# BTsoundCard_Proto_R1.net
KiCad netlist of a schematic drawn in EAGLE
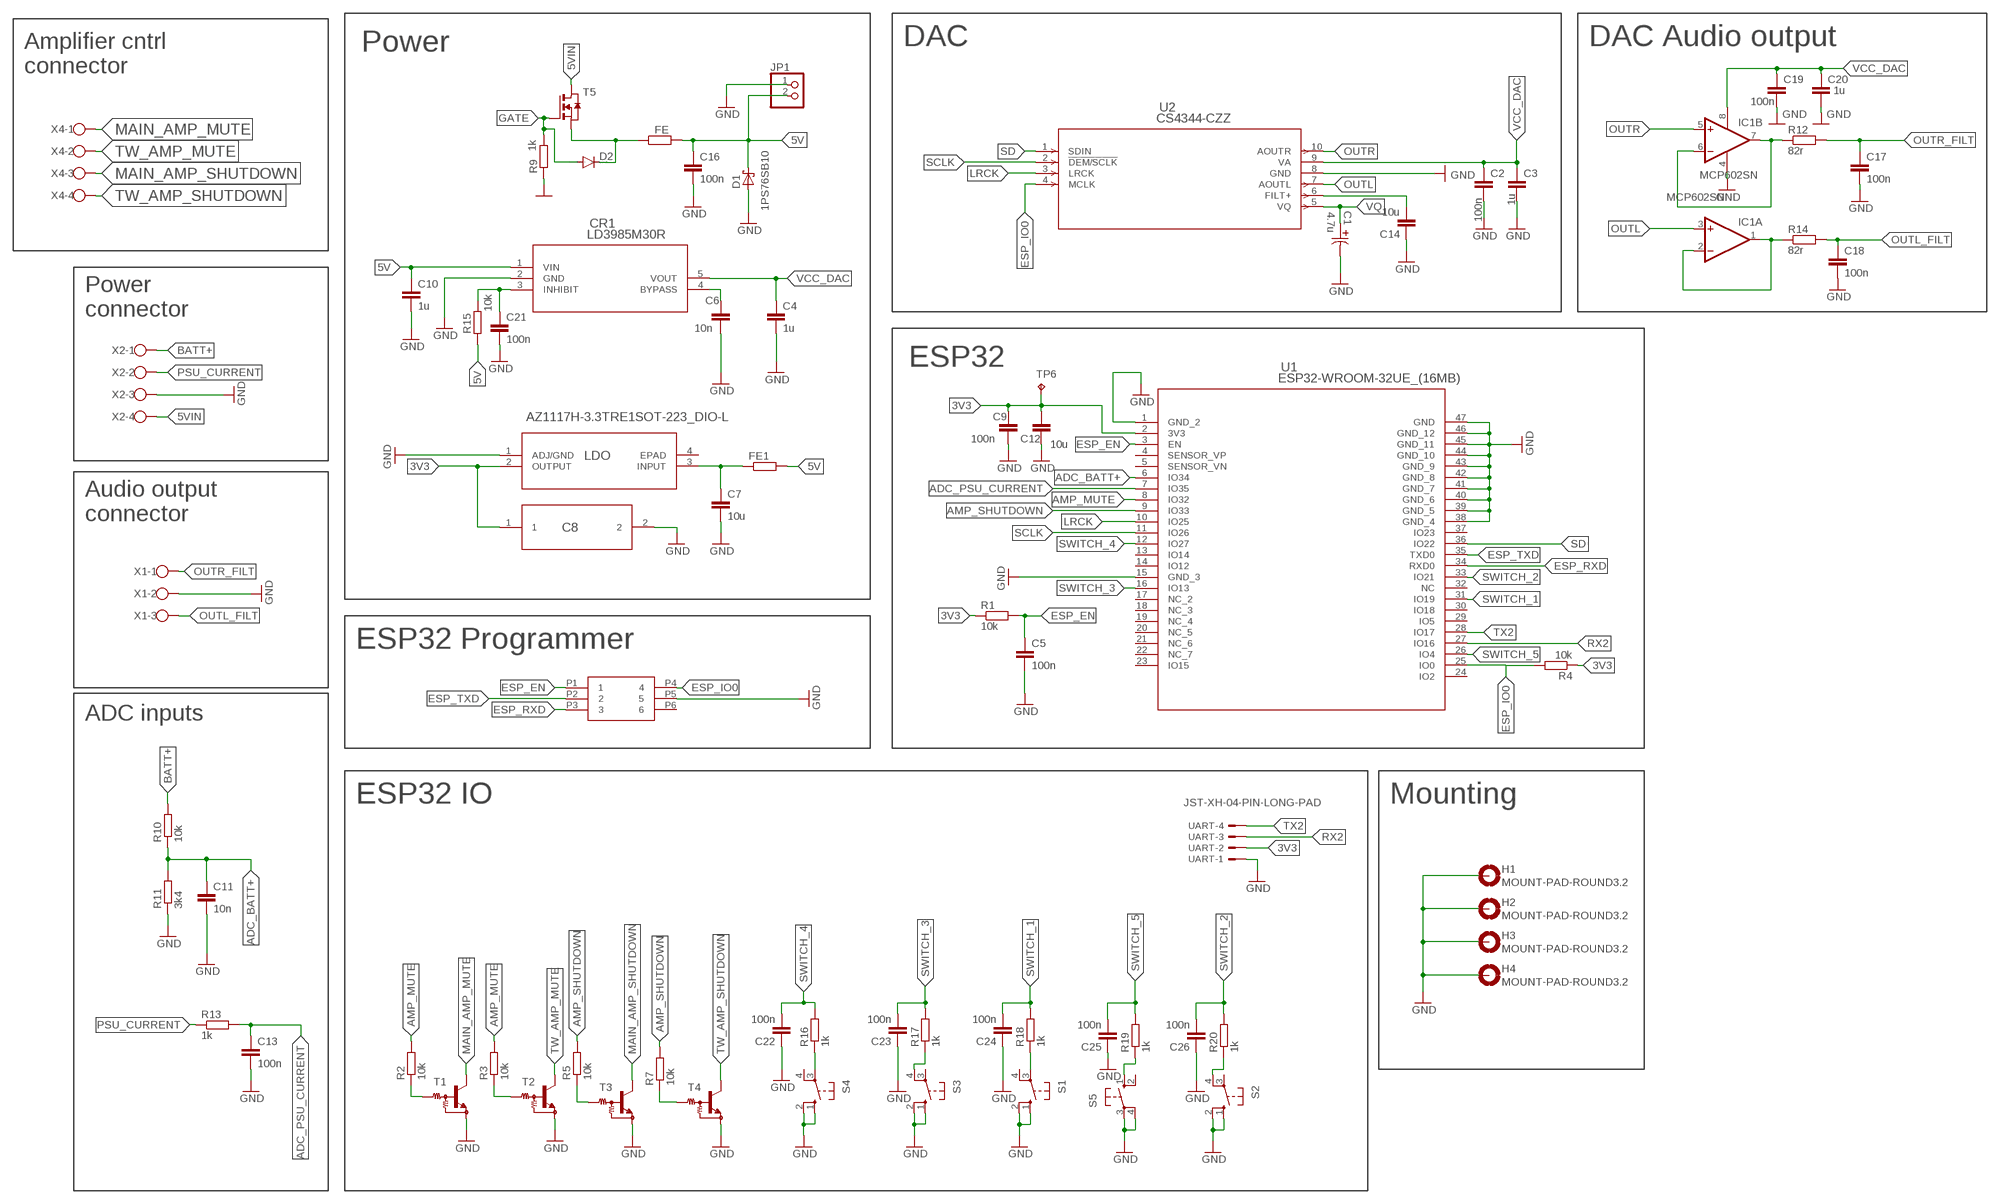
[diagram p0: schematic, sheet 1]

(export (version "E")
  (design (tool "Eeschema 10.0.6"))
  (components
    (comp (ref "C1")
      (value "4.7u")
      (footprint "eagle-import:CAP_EEFK_B_PAN-M")
      (fields (field (name "MANUFACTURER_PART_NUMBER") "EEEFK1H4R7R"))
      (libsource (lib "eagle-import") (part "EEEFK1H4R7RCAP_EEFK_B_PAN-M"))
    )
    (comp (ref "C2")
      (value "100n")
      (footprint "eagle-import:C0603")
      (libsource (lib "eagle-import") (part "C-EUC0603"))
    )
    (comp (ref "C3")
      (value "1u")
      (footprint "eagle-import:C0603")
      (libsource (lib "eagle-import") (part "C-EUC0603"))
    )
    (comp (ref "C4")
      (value "1u")
      (footprint "eagle-import:C0603")
      (libsource (lib "eagle-import") (part "C-EUC0603"))
    )
    (comp (ref "C5")
      (value "100n")
      (footprint "eagle-import:C0603")
      (libsource (lib "eagle-import") (part "C-EUC0603"))
    )
    (comp (ref "C6")
      (value "10n")
      (footprint "eagle-import:C0603")
      (libsource (lib "eagle-import") (part "C-EUC0603"))
    )
    (comp (ref "C7")
      (value "10u")
      (footprint "eagle-import:C0805")
      (libsource (lib "eagle-import") (part "C-EUC0805"))
    )
    (comp (ref "C8")
      (value "TPSC336K010R0375")
      (footprint "eagle-import:TPSC336K010R0375_AVX")
      (fields (field (name "COPYRIGHT") "Copyright (C) 2018 Accelerated Designs. All rights reserved"))
      (libsource (lib "eagle-import") (part "TPSC336K010R0375"))
    )
    (comp (ref "C9")
      (value "100n")
      (footprint "eagle-import:C0603")
      (libsource (lib "eagle-import") (part "C-EUC0603"))
    )
    (comp (ref "C10")
      (value "1u")
      (footprint "eagle-import:C0603")
      (libsource (lib "eagle-import") (part "C-EUC0603"))
    )
    (comp (ref "C11")
      (value "10n")
      (footprint "eagle-import:C0603")
      (libsource (lib "eagle-import") (part "C-EUC0603"))
    )
    (comp (ref "C12")
      (value "10u")
      (footprint "eagle-import:C0805")
      (libsource (lib "eagle-import") (part "C-EUC0805"))
    )
    (comp (ref "C13")
      (value "100n")
      (footprint "eagle-import:C0603")
      (libsource (lib "eagle-import") (part "C-EUC0603"))
    )
    (comp (ref "C14")
      (value "10u")
      (footprint "eagle-import:C0805")
      (libsource (lib "eagle-import") (part "C-EUC0805"))
    )
    (comp (ref "C16")
      (value "100n")
      (footprint "eagle-import:C0603")
      (libsource (lib "eagle-import") (part "C-EUC0603"))
    )
    (comp (ref "C17")
      (value "100n")
      (footprint "eagle-import:C0603")
      (libsource (lib "eagle-import") (part "C-EUC0603"))
    )
    (comp (ref "C18")
      (value "100n")
      (footprint "eagle-import:C0603")
      (libsource (lib "eagle-import") (part "C-EUC0603"))
    )
    (comp (ref "C19")
      (value "100n")
      (footprint "eagle-import:C0603")
      (libsource (lib "eagle-import") (part "C-EUC0603"))
    )
    (comp (ref "C20")
      (value "1u")
      (footprint "eagle-import:C0603")
      (libsource (lib "eagle-import") (part "C-EUC0603"))
    )
    (comp (ref "C21")
      (value "100n")
      (footprint "eagle-import:C0603")
      (libsource (lib "eagle-import") (part "C-EUC0603"))
    )
    (comp (ref "C22")
      (value "100n")
      (footprint "eagle-import:C0603")
      (libsource (lib "eagle-import") (part "C-EUC0603"))
    )
    (comp (ref "C23")
      (value "100n")
      (footprint "eagle-import:C0603")
      (libsource (lib "eagle-import") (part "C-EUC0603"))
    )
    (comp (ref "C24")
      (value "100n")
      (footprint "eagle-import:C0603")
      (libsource (lib "eagle-import") (part "C-EUC0603"))
    )
    (comp (ref "C25")
      (value "100n")
      (footprint "eagle-import:C0603")
      (libsource (lib "eagle-import") (part "C-EUC0603"))
    )
    (comp (ref "C26")
      (value "100n")
      (footprint "eagle-import:C0603")
      (libsource (lib "eagle-import") (part "C-EUC0603"))
    )
    (comp (ref "CR1")
      (value "LD3985M30R")
      (footprint "eagle-import:SOT23-5L_STM")
      (fields (field (name "COPYRIGHT") "Copyright (C) 2023 Ultra Librarian. All rights reserved."))
      (libsource (lib "eagle-import") (part "LD3985M30R"))
    )
    (comp (ref "D1")
      (value "1PS76SB10")
      (footprint "eagle-import:SOD323(F)")
      (libsource (lib "eagle-import") (part "1PS76SB10"))
    )
    (comp (ref "D2")
      (value "5.1V")
      (footprint "eagle-import:MINIMELF")
      (libsource (lib "eagle-import") (part "DIODE-MINIMELF"))
    )
    (comp (ref "FE")
      (value "R-EU_R0805")
      (footprint "eagle-import:R0805")
      (libsource (lib "eagle-import") (part "R-EU_R0805"))
    )
    (comp (ref "FE1")
      (value "R-EU_R0805")
      (footprint "eagle-import:R0805")
      (libsource (lib "eagle-import") (part "R-EU_R0805"))
    )
    (comp (ref "H1")
      (value "MOUNT-PAD-ROUND3.2")
      (footprint "eagle-import:3,2-PAD")
      (libsource (lib "eagle-import") (part "MOUNT-PAD-ROUND3.2"))
    )
    (comp (ref "H2")
      (value "MOUNT-PAD-ROUND3.2")
      (footprint "eagle-import:3,2-PAD")
      (libsource (lib "eagle-import") (part "MOUNT-PAD-ROUND3.2"))
    )
    (comp (ref "H3")
      (value "MOUNT-PAD-ROUND3.2")
      (footprint "eagle-import:3,2-PAD")
      (libsource (lib "eagle-import") (part "MOUNT-PAD-ROUND3.2"))
    )
    (comp (ref "H4")
      (value "MOUNT-PAD-ROUND3.2")
      (footprint "eagle-import:3,2-PAD")
      (libsource (lib "eagle-import") (part "MOUNT-PAD-ROUND3.2"))
    )
    (comp (ref "IC1")
      (value "MCP602SN")
      (footprint "eagle-import:SO08")
      (libsource (lib "eagle-import") (part "MCP602SN"))
    )
    (comp (ref "JP1")
      (value "PINHD-1X2")
      (footprint "eagle-import:1X02")
      (libsource (lib "eagle-import") (part "PINHD-1X2"))
    )
    (comp (ref "LDO")
      (value "AZ1117H-3.3TRE1SOT-223_DIO-L")
      (footprint "eagle-import:SOT-223_DIO-L")
      (fields (field (name "MANUFACTURER_PART_NUMBER") "AZ1117H-3.3TRE1"))
      (libsource (lib "eagle-import") (part "AZ1117H-3.3TRE1SOT-223_DIO-L"))
    )
    (comp (ref "R1")
      (value "10k")
      (footprint "eagle-import:R0603")
      (libsource (lib "eagle-import") (part "R-EU_R0603"))
    )
    (comp (ref "R2")
      (value "10k")
      (footprint "eagle-import:R0603")
      (libsource (lib "eagle-import") (part "R-EU_R0603"))
    )
    (comp (ref "R3")
      (value "10k")
      (footprint "eagle-import:R0603")
      (libsource (lib "eagle-import") (part "R-EU_R0603"))
    )
    (comp (ref "R4")
      (value "10k")
      (footprint "eagle-import:R0603")
      (libsource (lib "eagle-import") (part "R-EU_R0603"))
    )
    (comp (ref "R5")
      (value "10k")
      (footprint "eagle-import:R0603")
      (libsource (lib "eagle-import") (part "R-EU_R0603"))
    )
    (comp (ref "R7")
      (value "10k")
      (footprint "eagle-import:R0603")
      (libsource (lib "eagle-import") (part "R-EU_R0603"))
    )
    (comp (ref "R9")
      (value "1k")
      (footprint "eagle-import:R1206")
      (libsource (lib "eagle-import") (part "R-EU_R1206"))
    )
    (comp (ref "R10")
      (value "10k")
      (footprint "eagle-import:R0805")
      (libsource (lib "eagle-import") (part "R-EU_R0805"))
    )
    (comp (ref "R11")
      (value "3k4")
      (footprint "eagle-import:R0603")
      (libsource (lib "eagle-import") (part "R-EU_R0603"))
    )
    (comp (ref "R12")
      (value "82r")
      (footprint "eagle-import:R1206")
      (libsource (lib "eagle-import") (part "R-EU_R1206"))
    )
    (comp (ref "R13")
      (value "1k")
      (footprint "eagle-import:R0603")
      (libsource (lib "eagle-import") (part "R-EU_R0603"))
    )
    (comp (ref "R14")
      (value "82r")
      (footprint "eagle-import:R1206")
      (libsource (lib "eagle-import") (part "R-EU_R1206"))
    )
    (comp (ref "R15")
      (value "10k")
      (footprint "eagle-import:R0603")
      (libsource (lib "eagle-import") (part "R-EU_R0603"))
    )
    (comp (ref "R16")
      (value "1k")
      (footprint "eagle-import:R0603")
      (libsource (lib "eagle-import") (part "R-EU_R0603"))
    )
    (comp (ref "R17")
      (value "1k")
      (footprint "eagle-import:R0603")
      (libsource (lib "eagle-import") (part "R-EU_R0603"))
    )
    (comp (ref "R18")
      (value "1k")
      (footprint "eagle-import:R0603")
      (libsource (lib "eagle-import") (part "R-EU_R0603"))
    )
    (comp (ref "R19")
      (value "1k")
      (footprint "eagle-import:R0603")
      (libsource (lib "eagle-import") (part "R-EU_R0603"))
    )
    (comp (ref "R20")
      (value "1k")
      (footprint "eagle-import:R0603")
      (libsource (lib "eagle-import") (part "R-EU_R0603"))
    )
    (comp (ref "S1")
      (value "10-XX")
      (footprint "eagle-import:B3F-10XX")
      (fields (field (name "MPN") "B3F-1000"))
      (libsource (lib "eagle-import") (part "10-XX"))
    )
    (comp (ref "S2")
      (value "10-XX")
      (footprint "eagle-import:B3F-10XX")
      (fields (field (name "MPN") "B3F-1000"))
      (libsource (lib "eagle-import") (part "10-XX"))
    )
    (comp (ref "S3")
      (value "10-XX")
      (footprint "eagle-import:B3F-10XX")
      (fields (field (name "MPN") "B3F-1000"))
      (libsource (lib "eagle-import") (part "10-XX"))
    )
    (comp (ref "S4")
      (value "10-XX")
      (footprint "eagle-import:B3F-10XX")
      (fields (field (name "MPN") "B3F-1000"))
      (libsource (lib "eagle-import") (part "10-XX"))
    )
    (comp (ref "S5")
      (value "10-XX")
      (footprint "eagle-import:B3F-10XX")
      (fields (field (name "MPN") "B3F-1000"))
      (libsource (lib "eagle-import") (part "10-XX"))
    )
    (comp (ref "T1")
      (value "MUN2212T1-NPN_DRIVER-SC59-BEC")
      (footprint "eagle-import:SC59-BEC")
      (libsource (lib "eagle-import") (part "-NPN_DRIVER-SC59-BECMUN2212T1"))
    )
    (comp (ref "T2")
      (value "MUN2212T1-NPN_DRIVER-SC59-BEC")
      (footprint "eagle-import:SC59-BEC")
      (libsource (lib "eagle-import") (part "-NPN_DRIVER-SC59-BECMUN2212T1"))
    )
    (comp (ref "T3")
      (value "MUN2212T1-NPN_DRIVER-SC59-BEC")
      (footprint "eagle-import:SC59-BEC")
      (libsource (lib "eagle-import") (part "-NPN_DRIVER-SC59-BECMUN2212T1"))
    )
    (comp (ref "T4")
      (value "MUN2212T1-NPN_DRIVER-SC59-BEC")
      (footprint "eagle-import:SC59-BEC")
      (libsource (lib "eagle-import") (part "-NPN_DRIVER-SC59-BECMUN2212T1"))
    )
    (comp (ref "T5")
      (value "NMOSSOT23")
      (footprint "eagle-import:SOT-23")
      (libsource (lib "eagle-import") (part "NMOSSOT23"))
    )
    (comp (ref "TP6")
      (value "TPPAD1-13")
      (footprint "eagle-import:P1-13")
      (libsource (lib "eagle-import") (part "TPPAD1-13"))
    )
    (comp (ref "U$3")
      (value "3X2")
      (footprint "eagle-import:2X3")
      (libsource (lib "eagle-import") (part "3X2"))
    )
    (comp (ref "U1")
      (value "ESP32-WROOM-32UE_(16MB)")
      (footprint "eagle-import:IC38_ESP32-WROOM-32UE_(16MB)_E")
      (fields
        (field (name "MANUFACTURER_PART_NUMBER") "ESP32-WROOM-32UE (16MB)")
        (field (name "COPYRIGHT") "Copyright (C) 2022 Ultra Librarian. All rights reserved.")
      )
      (libsource (lib "eagle-import") (part "ESP32-WROOM-32UE_(16MB)"))
    )
    (comp (ref "U2")
      (value "CS4344-CZZ")
      (footprint "eagle-import:CIR-TSSOP-10")
      (fields (field (name "COPYRIGHT") "Copyright (C) 2023 Ultra Librarian. All rights reserved."))
      (libsource (lib "eagle-import") (part "CS4344-CZZ"))
    )
    (comp (ref "UART")
      (value "JST-XH-04-PIN-LONG-PAD")
      (footprint "eagle-import:JST-XH-04-PACKAGE-LONG-PAD")
      (libsource (lib "eagle-import") (part "JST-XH-04-PIN-LONG-PAD"))
    )
    (comp (ref "X1")
      (value "W237-103")
      (footprint "eagle-import:W237-103")
      (fields (field (name "MPN") "237-103"))
      (libsource (lib "eagle-import") (part "W237-103"))
    )
    (comp (ref "X2")
      (value "W237-4")
      (footprint "eagle-import:W237-4")
      (libsource (lib "eagle-import") (part "W237-4"))
    )
    (comp (ref "X4")
      (value "W237-4")
      (footprint "eagle-import:W237-4")
      (libsource (lib "eagle-import") (part "W237-4"))
    )
  )
  (nets
    (net (code "1") (name "3V3") (class "Default")
      (node (ref "C12") (pin "2") (pinfunction "2_2") (pintype "passive"))
      (node (ref "C8") (pin "1") (pinfunction "1_1") (pintype "passive"))
      (node (ref "C9") (pin "1") (pinfunction "1_1") (pintype "passive"))
      (node (ref "LDO") (pin "2") (pinfunction "OUTPUT_2") (pintype "output"))
      (node (ref "R1") (pin "1") (pinfunction "1_1") (pintype "passive"))
      (node (ref "R4") (pin "1") (pinfunction "1_1") (pintype "passive"))
      (node (ref "TP6") (pin "TP") (pinfunction "TP_TP") (pintype "input"))
      (node (ref "U1") (pin "2") (pinfunction "3V3_2") (pintype "passive"))
      (node (ref "UART") (pin "2") (pinfunction "S_2") (pintype "passive"))
    )
    (net (code "2") (name "5V") (class "Default")
      (node (ref "C10") (pin "1") (pinfunction "1_1") (pintype "passive"))
      (node (ref "C16") (pin "1") (pinfunction "1_1") (pintype "passive"))
      (node (ref "CR1") (pin "1") (pinfunction "VIN_1") (pintype "power_in"))
      (node (ref "D1") (pin "1") (pinfunction "K_1") (pintype "passive"))
      (node (ref "FE") (pin "2") (pinfunction "2_2") (pintype "passive"))
      (node (ref "FE1") (pin "2") (pinfunction "2_2") (pintype "passive"))
      (node (ref "JP1") (pin "2") (pinfunction "2_2") (pintype "passive"))
      (node (ref "R15") (pin "1") (pinfunction "1_1") (pintype "passive"))
    )
    (net (code "3") (name "5VIN") (class "Default")
      (node (ref "T5") (pin "1") (pinfunction "D_1") (pintype "passive"))
      (node (ref "X2") (pin "4") (pinfunction "KL_4") (pintype "passive"))
    )
    (net (code "4") (name "ADC_BATT+") (class "Default")
      (node (ref "C11") (pin "1") (pinfunction "1_1") (pintype "passive"))
      (node (ref "R10") (pin "1") (pinfunction "1_1") (pintype "passive"))
      (node (ref "R11") (pin "2") (pinfunction "2_2") (pintype "passive"))
      (node (ref "U1") (pin "6") (pinfunction "IO34_6") (pintype "passive"))
    )
    (net (code "5") (name "ADC_PSU_CURRENT") (class "Default")
      (node (ref "C13") (pin "1") (pinfunction "1_1") (pintype "passive"))
      (node (ref "R13") (pin "2") (pinfunction "2_2") (pintype "passive"))
      (node (ref "U1") (pin "7") (pinfunction "IO35_7") (pintype "passive"))
    )
    (net (code "6") (name "AMP_MUTE") (class "Default")
      (node (ref "R2") (pin "2") (pinfunction "2_2") (pintype "passive"))
      (node (ref "R3") (pin "2") (pinfunction "2_2") (pintype "passive"))
      (node (ref "U1") (pin "8") (pinfunction "IO32_8") (pintype "passive"))
    )
    (net (code "7") (name "AMP_SHUTDOWN") (class "Default")
      (node (ref "R5") (pin "2") (pinfunction "2_2") (pintype "passive"))
      (node (ref "R7") (pin "2") (pinfunction "2_2") (pintype "passive"))
      (node (ref "U1") (pin "9") (pinfunction "IO33_9") (pintype "passive"))
    )
    (net (code "8") (name "BATT+") (class "Default")
      (node (ref "R10") (pin "2") (pinfunction "2_2") (pintype "passive"))
      (node (ref "X2") (pin "1") (pinfunction "KL_1") (pintype "passive"))
    )
    (net (code "9") (name "ESP_EN") (class "Default")
      (node (ref "C5") (pin "1") (pinfunction "1_1") (pintype "passive"))
      (node (ref "R1") (pin "2") (pinfunction "2_2") (pintype "passive"))
      (node (ref "U$3") (pin "P1") (pinfunction "1_P1") (pintype "bidirectional"))
      (node (ref "U1") (pin "3") (pinfunction "EN_3") (pintype "passive"))
    )
    (net (code "10") (name "ESP_IO0") (class "Default")
      (node (ref "R4") (pin "2") (pinfunction "2_2") (pintype "passive"))
      (node (ref "U$3") (pin "P4") (pinfunction "4_P4") (pintype "bidirectional"))
      (node (ref "U1") (pin "25") (pinfunction "IO0_25") (pintype "passive"))
      (node (ref "U2") (pin "4") (pinfunction "MCLK_4") (pintype "input"))
    )
    (net (code "11") (name "ESP_RXD") (class "Default")
      (node (ref "U$3") (pin "P3") (pinfunction "3_P3") (pintype "bidirectional"))
      (node (ref "U1") (pin "34") (pinfunction "RXD0_34") (pintype "passive"))
    )
    (net (code "12") (name "ESP_TXD") (class "Default")
      (node (ref "U$3") (pin "P2") (pinfunction "2_P2") (pintype "bidirectional"))
      (node (ref "U1") (pin "35") (pinfunction "TXD0_35") (pintype "passive"))
    )
    (net (code "13") (name "GATE") (class "Default")
      (node (ref "D2") (pin "A") (pinfunction "A_A") (pintype "passive"))
      (node (ref "R9") (pin "2") (pinfunction "2_2") (pintype "passive"))
      (node (ref "T5") (pin "3") (pinfunction "G_3") (pintype "passive"))
    )
    (net (code "14") (name "GND") (class "Default")
      (node (ref "C1") (pin "2") (pinfunction "2_2") (pintype "passive"))
      (node (ref "C10") (pin "2") (pinfunction "2_2") (pintype "passive"))
      (node (ref "C11") (pin "2") (pinfunction "2_2") (pintype "passive"))
      (node (ref "C12") (pin "1") (pinfunction "1_1") (pintype "passive"))
      (node (ref "C13") (pin "2") (pinfunction "2_2") (pintype "passive"))
      (node (ref "C14") (pin "1") (pinfunction "1_1") (pintype "passive"))
      (node (ref "C16") (pin "2") (pinfunction "2_2") (pintype "passive"))
      (node (ref "C17") (pin "2") (pinfunction "2_2") (pintype "passive"))
      (node (ref "C18") (pin "2") (pinfunction "2_2") (pintype "passive"))
      (node (ref "C19") (pin "2") (pinfunction "2_2") (pintype "passive"))
      (node (ref "C2") (pin "2") (pinfunction "2_2") (pintype "passive"))
      (node (ref "C20") (pin "2") (pinfunction "2_2") (pintype "passive"))
      (node (ref "C21") (pin "2") (pinfunction "2_2") (pintype "passive"))
      (node (ref "C22") (pin "1") (pinfunction "1_1") (pintype "passive"))
      (node (ref "C23") (pin "1") (pinfunction "1_1") (pintype "passive"))
      (node (ref "C24") (pin "1") (pinfunction "1_1") (pintype "passive"))
      (node (ref "C25") (pin "1") (pinfunction "1_1") (pintype "passive"))
      (node (ref "C26") (pin "1") (pinfunction "1_1") (pintype "passive"))
      (node (ref "C3") (pin "2") (pinfunction "2_2") (pintype "passive"))
      (node (ref "C4") (pin "2") (pinfunction "2_2") (pintype "passive"))
      (node (ref "C5") (pin "2") (pinfunction "2_2") (pintype "passive"))
      (node (ref "C6") (pin "2") (pinfunction "2_2") (pintype "passive"))
      (node (ref "C7") (pin "2") (pinfunction "2_2") (pintype "passive"))
      (node (ref "C8") (pin "2") (pinfunction "2_2") (pintype "passive"))
      (node (ref "C9") (pin "2") (pinfunction "2_2") (pintype "passive"))
      (node (ref "CR1") (pin "2") (pinfunction "GND_2") (pintype "passive"))
      (node (ref "D1") (pin "2") (pinfunction "A_2") (pintype "passive"))
      (node (ref "H1") (pin "B3,2") (pinfunction "MOUNT_B3,2") (pintype "passive"))
      (node (ref "H2") (pin "B3,2") (pinfunction "MOUNT_B3,2") (pintype "passive"))
      (node (ref "H3") (pin "B3,2") (pinfunction "MOUNT_B3,2") (pintype "passive"))
      (node (ref "H4") (pin "B3,2") (pinfunction "MOUNT_B3,2") (pintype "passive"))
      (node (ref "IC1") (pin "4") (pinfunction "V-_4") (pintype "power_in"))
      (node (ref "JP1") (pin "1") (pinfunction "1_1") (pintype "passive"))
      (node (ref "LDO") (pin "1") (pinfunction "ADJ/GND_1") (pintype "bidirectional"))
      (node (ref "R11") (pin "1") (pinfunction "1_1") (pintype "passive"))
      (node (ref "R9") (pin "1") (pinfunction "1_1") (pintype "passive"))
      (node (ref "S1") (pin "1") (pinfunction "S_1") (pintype "passive"))
      (node (ref "S1") (pin "2") (pinfunction "S1_2") (pintype "passive"))
      (node (ref "S2") (pin "1") (pinfunction "S_1") (pintype "passive"))
      (node (ref "S2") (pin "2") (pinfunction "S1_2") (pintype "passive"))
      (node (ref "S3") (pin "1") (pinfunction "S_1") (pintype "passive"))
      (node (ref "S3") (pin "2") (pinfunction "S1_2") (pintype "passive"))
      (node (ref "S4") (pin "1") (pinfunction "S_1") (pintype "passive"))
      (node (ref "S4") (pin "2") (pinfunction "S1_2") (pintype "passive"))
      (node (ref "S5") (pin "3") (pinfunction "P_3") (pintype "passive"))
      (node (ref "S5") (pin "4") (pinfunction "P1_4") (pintype "passive"))
      (node (ref "T1") (pin "E") (pinfunction "E_E") (pintype "passive"))
      (node (ref "T2") (pin "E") (pinfunction "E_E") (pintype "passive"))
      (node (ref "T3") (pin "E") (pinfunction "E_E") (pintype "passive"))
      (node (ref "T4") (pin "E") (pinfunction "E_E") (pintype "passive"))
      (node (ref "U$3") (pin "P5") (pinfunction "5_P5") (pintype "bidirectional"))
      (node (ref "U1") (pin "1") (pinfunction "GND_2_1") (pintype "passive"))
      (node (ref "U1") (pin "15") (pinfunction "GND_3_15") (pintype "passive"))
      (node (ref "U1") (pin "38") (pinfunction "GND_4_38") (pintype "passive"))
      (node (ref "U1") (pin "39") (pinfunction "GND_5_39") (pintype "passive"))
      (node (ref "U1") (pin "40") (pinfunction "GND_6_40") (pintype "passive"))
      (node (ref "U1") (pin "41") (pinfunction "GND_7_41") (pintype "passive"))
      (node (ref "U1") (pin "42") (pinfunction "GND_8_42") (pintype "passive"))
      (node (ref "U1") (pin "43") (pinfunction "GND_9_43") (pintype "passive"))
      (node (ref "U1") (pin "44") (pinfunction "GND_10_44") (pintype "passive"))
      (node (ref "U1") (pin "45") (pinfunction "GND_11_45") (pintype "passive"))
      (node (ref "U1") (pin "46") (pinfunction "GND_12_46") (pintype "passive"))
      (node (ref "U1") (pin "47") (pinfunction "GND_47") (pintype "passive"))
      (node (ref "U2") (pin "8") (pinfunction "GND_8") (pintype "power_in"))
      (node (ref "UART") (pin "1") (pinfunction "S_1") (pintype "passive"))
      (node (ref "X1") (pin "2") (pinfunction "KL_2") (pintype "passive"))
      (node (ref "X2") (pin "3") (pinfunction "KL_3") (pintype "passive"))
    )
    (net (code "15") (name "LRCK") (class "Default")
      (node (ref "U1") (pin "10") (pinfunction "IO25_10") (pintype "passive"))
      (node (ref "U2") (pin "3") (pinfunction "LRCK_3") (pintype "input"))
    )
    (net (code "16") (name "MAIN_AMP_MUTE") (class "Default")
      (node (ref "T1") (pin "C") (pinfunction "C_C") (pintype "passive"))
      (node (ref "X4") (pin "1") (pinfunction "KL_1") (pintype "passive"))
    )
    (net (code "17") (name "MAIN_AMP_SHUTDOWN") (class "Default")
      (node (ref "T3") (pin "C") (pinfunction "C_C") (pintype "passive"))
      (node (ref "X4") (pin "3") (pinfunction "KL_3") (pintype "passive"))
    )
    (net (code "18") (name "Net-(CR1-BYPASS)") (class "Default")
      (node (ref "C6") (pin "1") (pinfunction "1_1") (pintype "passive"))
      (node (ref "CR1") (pin "4") (pinfunction "BYPASS_4") (pintype "passive"))
    )
    (net (code "19") (name "Net-(CR1-INHIBIT)") (class "Default")
      (node (ref "C21") (pin "1") (pinfunction "1_1") (pintype "passive"))
      (node (ref "CR1") (pin "3") (pinfunction "INHIBIT_3") (pintype "input"))
      (node (ref "R15") (pin "2") (pinfunction "2_2") (pintype "passive"))
    )
    (net (code "20") (name "Net-(IC1A--IN)") (class "Default")
      (node (ref "IC1") (pin "1") (pinfunction "OUT_1") (pintype "output"))
      (node (ref "IC1") (pin "2") (pinfunction "-IN_2") (pintype "input"))
      (node (ref "R14") (pin "1") (pinfunction "1_1") (pintype "passive"))
    )
    (net (code "21") (name "Net-(IC1B--IN)") (class "Default")
      (node (ref "IC1") (pin "6") (pinfunction "-IN_6") (pintype "input"))
      (node (ref "IC1") (pin "7") (pinfunction "OUT_7") (pintype "output"))
      (node (ref "R12") (pin "1") (pinfunction "1_1") (pintype "passive"))
    )
    (net (code "22") (name "Net-(LDO-INPUT)") (class "Default")
      (node (ref "C7") (pin "1") (pinfunction "1_1") (pintype "passive"))
      (node (ref "FE1") (pin "1") (pinfunction "1_1") (pintype "passive"))
      (node (ref "LDO") (pin "3") (pinfunction "INPUT_3") (pintype "input"))
    )
    (net (code "23") (name "Net-(R2-Pad1)") (class "Default")
      (node (ref "R2") (pin "1") (pinfunction "1_1") (pintype "passive"))
      (node (ref "T1") (pin "B") (pinfunction "B_B") (pintype "passive"))
    )
    (net (code "24") (name "Net-(R3-Pad1)") (class "Default")
      (node (ref "R3") (pin "1") (pinfunction "1_1") (pintype "passive"))
      (node (ref "T2") (pin "B") (pinfunction "B_B") (pintype "passive"))
    )
    (net (code "25") (name "Net-(R5-Pad1)") (class "Default")
      (node (ref "R5") (pin "1") (pinfunction "1_1") (pintype "passive"))
      (node (ref "T3") (pin "B") (pinfunction "B_B") (pintype "passive"))
    )
    (net (code "26") (name "Net-(R7-Pad1)") (class "Default")
      (node (ref "R7") (pin "1") (pinfunction "1_1") (pintype "passive"))
      (node (ref "T4") (pin "B") (pinfunction "B_B") (pintype "passive"))
    )
    (net (code "27") (name "Net-(S1-P)") (class "Default")
      (node (ref "R18") (pin "1") (pinfunction "1_1") (pintype "passive"))
      (node (ref "S1") (pin "3") (pinfunction "P_3") (pintype "passive"))
    )
    (net (code "28") (name "Net-(S2-P1)") (class "Default")
      (node (ref "R20") (pin "1") (pinfunction "1_1") (pintype "passive"))
      (node (ref "S2") (pin "4") (pinfunction "P1_4") (pintype "passive"))
    )
    (net (code "29") (name "Net-(S3-P1)") (class "Default")
      (node (ref "R17") (pin "1") (pinfunction "1_1") (pintype "passive"))
      (node (ref "S3") (pin "4") (pinfunction "P1_4") (pintype "passive"))
    )
    (net (code "30") (name "Net-(S4-P)") (class "Default")
      (node (ref "R16") (pin "1") (pinfunction "1_1") (pintype "passive"))
      (node (ref "S4") (pin "3") (pinfunction "P_3") (pintype "passive"))
    )
    (net (code "31") (name "Net-(S5-S)") (class "Default")
      (node (ref "R19") (pin "1") (pinfunction "1_1") (pintype "passive"))
      (node (ref "S5") (pin "1") (pinfunction "S_1") (pintype "passive"))
    )
    (net (code "32") (name "Net-(T5-S)") (class "Default")
      (node (ref "D2") (pin "C") (pinfunction "C_C") (pintype "passive"))
      (node (ref "FE") (pin "1") (pinfunction "1_1") (pintype "passive"))
      (node (ref "T5") (pin "2") (pinfunction "S_2") (pintype "passive"))
    )
    (net (code "33") (name "Net-(U2-FILT+)") (class "Default")
      (node (ref "C14") (pin "2") (pinfunction "2_2") (pintype "passive"))
      (node (ref "U2") (pin "6") (pinfunction "FILT+_6") (pintype "output"))
    )
    (net (code "34") (name "OUTL") (class "Default")
      (node (ref "IC1") (pin "3") (pinfunction "+IN_3") (pintype "input"))
      (node (ref "U2") (pin "7") (pinfunction "AOUTL_7") (pintype "output"))
    )
    (net (code "35") (name "OUTL_FILT") (class "Default")
      (node (ref "C18") (pin "1") (pinfunction "1_1") (pintype "passive"))
      (node (ref "R14") (pin "2") (pinfunction "2_2") (pintype "passive"))
      (node (ref "X1") (pin "3") (pinfunction "KL_3") (pintype "passive"))
    )
    (net (code "36") (name "OUTR") (class "Default")
      (node (ref "IC1") (pin "5") (pinfunction "+IN_5") (pintype "input"))
      (node (ref "U2") (pin "10") (pinfunction "AOUTR_10") (pintype "output"))
    )
    (net (code "37") (name "OUTR_FILT") (class "Default")
      (node (ref "C17") (pin "1") (pinfunction "1_1") (pintype "passive"))
      (node (ref "R12") (pin "2") (pinfunction "2_2") (pintype "passive"))
      (node (ref "X1") (pin "1") (pinfunction "KL_1") (pintype "passive"))
    )
    (net (code "38") (name "PSU_CURRENT") (class "Default")
      (node (ref "R13") (pin "1") (pinfunction "1_1") (pintype "passive"))
      (node (ref "X2") (pin "2") (pinfunction "KL_2") (pintype "passive"))
    )
    (net (code "39") (name "RX2") (class "Default")
      (node (ref "U1") (pin "27") (pinfunction "IO16_27") (pintype "passive"))
      (node (ref "UART") (pin "3") (pinfunction "S_3") (pintype "passive"))
    )
    (net (code "40") (name "SCLK") (class "Default")
      (node (ref "U1") (pin "11") (pinfunction "IO26_11") (pintype "passive"))
      (node (ref "U2") (pin "2") (pinfunction "~{DEM/SCLK}_2") (pintype "input"))
    )
    (net (code "41") (name "SD") (class "Default")
      (node (ref "U1") (pin "36") (pinfunction "IO22_36") (pintype "passive"))
      (node (ref "U2") (pin "1") (pinfunction "SDIN_1") (pintype "input"))
    )
    (net (code "42") (name "SWITCH_1") (class "Default")
      (node (ref "C24") (pin "2") (pinfunction "2_2") (pintype "passive"))
      (node (ref "R18") (pin "2") (pinfunction "2_2") (pintype "passive"))
      (node (ref "U1") (pin "31") (pinfunction "IO19_31") (pintype "passive"))
    )
    (net (code "43") (name "SWITCH_2") (class "Default")
      (node (ref "C26") (pin "2") (pinfunction "2_2") (pintype "passive"))
      (node (ref "R20") (pin "2") (pinfunction "2_2") (pintype "passive"))
      (node (ref "U1") (pin "33") (pinfunction "IO21_33") (pintype "passive"))
    )
    (net (code "44") (name "SWITCH_3") (class "Default")
      (node (ref "C23") (pin "2") (pinfunction "2_2") (pintype "passive"))
      (node (ref "R17") (pin "2") (pinfunction "2_2") (pintype "passive"))
      (node (ref "U1") (pin "16") (pinfunction "IO13_16") (pintype "passive"))
    )
    (net (code "45") (name "SWITCH_4") (class "Default")
      (node (ref "C22") (pin "2") (pinfunction "2_2") (pintype "passive"))
      (node (ref "R16") (pin "2") (pinfunction "2_2") (pintype "passive"))
      (node (ref "U1") (pin "12") (pinfunction "IO27_12") (pintype "passive"))
    )
    (net (code "46") (name "SWITCH_5") (class "Default")
      (node (ref "C25") (pin "2") (pinfunction "2_2") (pintype "passive"))
      (node (ref "R19") (pin "2") (pinfunction "2_2") (pintype "passive"))
      (node (ref "U1") (pin "26") (pinfunction "IO4_26") (pintype "passive"))
    )
    (net (code "47") (name "TW_AMP_MUTE") (class "Default")
      (node (ref "T2") (pin "C") (pinfunction "C_C") (pintype "passive"))
      (node (ref "X4") (pin "2") (pinfunction "KL_2") (pintype "passive"))
    )
    (net (code "48") (name "TW_AMP_SHUTDOWN") (class "Default")
      (node (ref "T4") (pin "C") (pinfunction "C_C") (pintype "passive"))
      (node (ref "X4") (pin "4") (pinfunction "KL_4") (pintype "passive"))
    )
    (net (code "49") (name "TX2") (class "Default")
      (node (ref "U1") (pin "28") (pinfunction "IO17_28") (pintype "passive"))
      (node (ref "UART") (pin "4") (pinfunction "S_4") (pintype "passive"))
    )
    (net (code "50") (name "VCC_DAC") (class "Default")
      (node (ref "C19") (pin "1") (pinfunction "1_1") (pintype "passive"))
      (node (ref "C2") (pin "1") (pinfunction "1_1") (pintype "passive"))
      (node (ref "C20") (pin "1") (pinfunction "1_1") (pintype "passive"))
      (node (ref "C3") (pin "1") (pinfunction "1_1") (pintype "passive"))
      (node (ref "C4") (pin "1") (pinfunction "1_1") (pintype "passive"))
      (node (ref "CR1") (pin "5") (pinfunction "VOUT_5") (pintype "power_in"))
      (node (ref "IC1") (pin "8") (pinfunction "V+_8") (pintype "power_in"))
      (node (ref "U2") (pin "9") (pinfunction "VA_9") (pintype "power_in"))
    )
    (net (code "51") (name "VQ") (class "Default")
      (node (ref "C1") (pin "1") (pinfunction "1_1") (pintype "passive"))
      (node (ref "U2") (pin "5") (pinfunction "VQ_5") (pintype "output"))
    )
    (net (code "52") (name "unconnected-(LDO-EPAD-Pad4)") (class "Default")
      (node (ref "LDO") (pin "4") (pinfunction "EPAD_4") (pintype "passive"))
    )
    (net (code "53") (name "unconnected-(S1-P1-Pad4)") (class "Default")
      (node (ref "S1") (pin "4") (pinfunction "P1_4") (pintype "passive"))
    )
    (net (code "54") (name "unconnected-(S2-P-Pad3)") (class "Default")
      (node (ref "S2") (pin "3") (pinfunction "P_3") (pintype "passive"))
    )
    (net (code "55") (name "unconnected-(S3-P-Pad3)") (class "Default")
      (node (ref "S3") (pin "3") (pinfunction "P_3") (pintype "passive"))
    )
    (net (code "56") (name "unconnected-(S4-P1-Pad4)") (class "Default")
      (node (ref "S4") (pin "4") (pinfunction "P1_4") (pintype "passive"))
    )
    (net (code "57") (name "unconnected-(S5-S1-Pad2)") (class "Default")
      (node (ref "S5") (pin "2") (pinfunction "S1_2") (pintype "passive"))
    )
    (net (code "58") (name "unconnected-(U$3-6-PadP6)") (class "Default")
      (node (ref "U$3") (pin "P6") (pinfunction "6_P6") (pintype "bidirectional"))
    )
    (net (code "59") (name "unconnected-(U1-IO2-Pad24)") (class "Default")
      (node (ref "U1") (pin "24") (pinfunction "IO2_24") (pintype "passive"))
    )
    (net (code "60") (name "unconnected-(U1-IO5-Pad29)") (class "Default")
      (node (ref "U1") (pin "29") (pinfunction "IO5_29") (pintype "passive"))
    )
    (net (code "61") (name "unconnected-(U1-IO12-Pad14)") (class "Default")
      (node (ref "U1") (pin "14") (pinfunction "IO12_14") (pintype "passive"))
    )
    (net (code "62") (name "unconnected-(U1-IO14-Pad13)") (class "Default")
      (node (ref "U1") (pin "13") (pinfunction "IO14_13") (pintype "passive"))
    )
    (net (code "63") (name "unconnected-(U1-IO15-Pad23)") (class "Default")
      (node (ref "U1") (pin "23") (pinfunction "IO15_23") (pintype "passive"))
    )
    (net (code "64") (name "unconnected-(U1-IO18-Pad30)") (class "Default")
      (node (ref "U1") (pin "30") (pinfunction "IO18_30") (pintype "passive"))
    )
    (net (code "65") (name "unconnected-(U1-IO23-Pad37)") (class "Default")
      (node (ref "U1") (pin "37") (pinfunction "IO23_37") (pintype "passive"))
    )
    (net (code "66") (name "unconnected-(U1-NC-Pad32)") (class "Default")
      (node (ref "U1") (pin "32") (pinfunction "NC_32") (pintype "passive"))
    )
    (net (code "67") (name "unconnected-(U1-NC_2-Pad17)") (class "Default")
      (node (ref "U1") (pin "17") (pinfunction "NC_2_17") (pintype "passive"))
    )
    (net (code "68") (name "unconnected-(U1-NC_3-Pad18)") (class "Default")
      (node (ref "U1") (pin "18") (pinfunction "NC_3_18") (pintype "passive"))
    )
    (net (code "69") (name "unconnected-(U1-NC_4-Pad19)") (class "Default")
      (node (ref "U1") (pin "19") (pinfunction "NC_4_19") (pintype "passive"))
    )
    (net (code "70") (name "unconnected-(U1-NC_5-Pad20)") (class "Default")
      (node (ref "U1") (pin "20") (pinfunction "NC_5_20") (pintype "passive"))
    )
    (net (code "71") (name "unconnected-(U1-NC_6-Pad21)") (class "Default")
      (node (ref "U1") (pin "21") (pinfunction "NC_6_21") (pintype "passive"))
    )
    (net (code "72") (name "unconnected-(U1-NC_7-Pad22)") (class "Default")
      (node (ref "U1") (pin "22") (pinfunction "NC_7_22") (pintype "passive"))
    )
    (net (code "73") (name "unconnected-(U1-SENSOR_VN-Pad5)") (class "Default")
      (node (ref "U1") (pin "5") (pinfunction "SENSOR_VN_5") (pintype "passive"))
    )
    (net (code "74") (name "unconnected-(U1-SENSOR_VP-Pad4)") (class "Default")
      (node (ref "U1") (pin "4") (pinfunction "SENSOR_VP_4") (pintype "passive"))
    )
  )
)
